# DB10005_PowerSwitch.net
KiCad netlist of a schematic drawn in Altium Designer
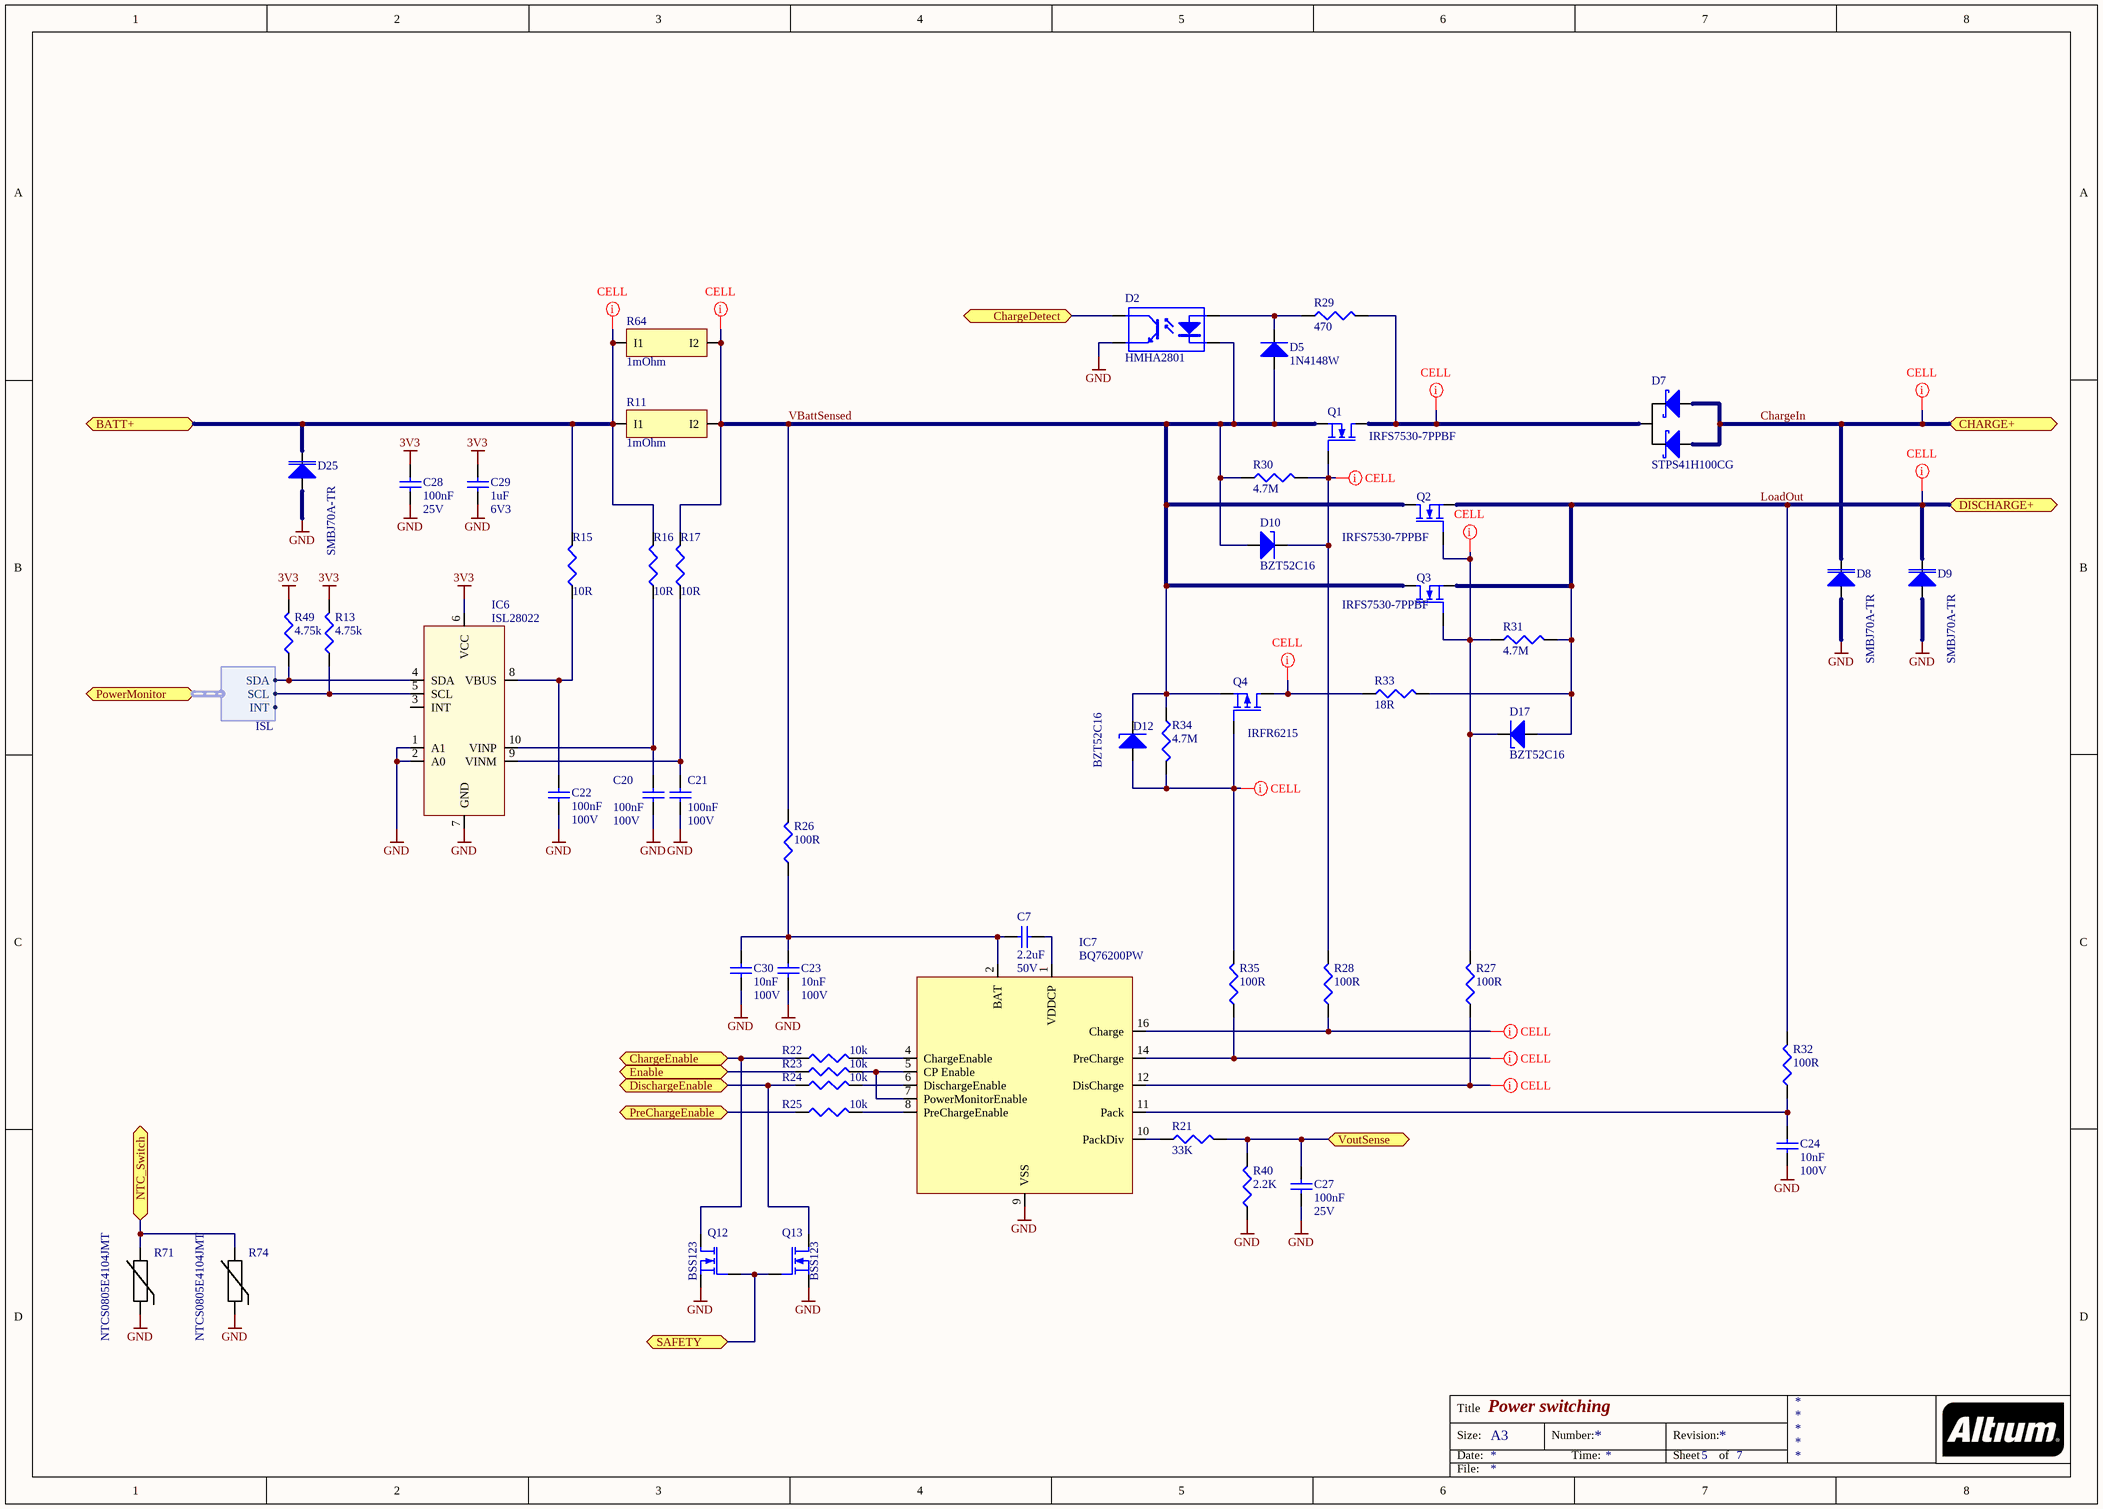
[diagram p0: DB10005_PowerSwitch.SchDoc]

(export (version "E")
  (design (tool "Eeschema 10.0.6"))
  (components
    (comp (ref "C7")
      (value "2.2uF")
      (footprint "C-0805")
      (description "Capacitor, 2.2uF, 50V,  X7R")
      (fields (field (name "VOLTAGE RATING") "50V"))
      (libsource (lib "AR_Capacitors_Ceramic") (part "2.2uF/0805/CER/50V"))
    )
    (comp (ref "C20")
      (value "100nF")
      (footprint "C-0805")
      (description "Capacitor, 100nF, 100V, X7R")
      (fields (field (name "VOLTAGE RATING") "100V"))
      (libsource (lib "AR_Capacitors_Ceramic") (part "100nF/0805/CER/100V"))
    )
    (comp (ref "C21")
      (value "100nF")
      (footprint "C-0805")
      (description "Capacitor, 100nF, 100V, X7R")
      (fields (field (name "VOLTAGE RATING") "100V"))
      (libsource (lib "AR_Capacitors_Ceramic") (part "100nF/0805/CER/100V"))
    )
    (comp (ref "C22")
      (value "100nF")
      (footprint "C-0805")
      (description "Capacitor, 100nF, 100V, X7R")
      (fields (field (name "VOLTAGE RATING") "100V"))
      (libsource (lib "AR_Capacitors_Ceramic") (part "100nF/0805/CER/100V"))
    )
    (comp (ref "C23")
      (value "10nF")
      (footprint "C-0805")
      (description "Capacitor, 10nF, 100V, X7R")
      (fields (field (name "VOLTAGE RATING") "100V"))
      (libsource (lib "AR_Capacitors_Ceramic") (part "10nF/0805/CER/100V"))
    )
    (comp (ref "C24")
      (value "10nF")
      (footprint "C-0805")
      (description "Capacitor, 10nF, 100V, X7R")
      (fields (field (name "VOLTAGE RATING") "100V"))
      (libsource (lib "AR_Capacitors_Ceramic") (part "10nF/0805/CER/100V"))
    )
    (comp (ref "C27")
      (value "100nF")
      (footprint "C0402")
      (description "Capacitor, 100nF, 25V, X7R")
      (fields (field (name "VOLTAGE RATING") "25V"))
      (libsource (lib "AR_Capacitors_Ceramic") (part "100nF/0402/CER/25V"))
    )
    (comp (ref "C28")
      (value "100nF")
      (footprint "C0402")
      (description "Capacitor, 100nF, 25V, X7R")
      (fields (field (name "VOLTAGE RATING") "25V"))
      (libsource (lib "AR_Capacitors_Ceramic") (part "100nF/0402/CER/25V"))
    )
    (comp (ref "C29")
      (value "1uF")
      (footprint "C0402")
      (description "Capacitor, 1uF, 6.3V, X5R")
      (fields (field (name "VOLTAGE RATING") "6V3"))
      (libsource (lib "AR_Capacitors_Ceramic") (part "1uF/0402/CER/6.3V"))
    )
    (comp (ref "C30")
      (value "10nF")
      (footprint "C-0805")
      (description "Capacitor, 10nF, 100V, X7R")
      (fields (field (name "VOLTAGE RATING") "100V"))
      (libsource (lib "AR_Capacitors_Ceramic") (part "10nF/0805/CER/100V"))
    )
    (comp (ref "D2")
      (value "HMHA2801")
      (footprint "FSOP4")
      (description "Optocoupler, Vout:80V, Iin:0.01A")
      (libsource (lib "AR_Optocouplers") (part "HMHA2801"))
    )
    (comp (ref "D5")
      (value "1N4148W")
      (footprint "SOD123")
      (description "Diode, Vrrm: 100V, If: 0.15A, Vf: 1V")
      (libsource (lib "AR_Diodes") (part "MMSD4148T1G"))
    )
    (comp (ref "D7")
      (value "STPS41H100CG")
      (footprint "D2-PAK")
      (description "100 V, 40 A, TO-263, 3 Pins, 900 mV")
      (libsource (lib "AR_Diodes") (part "STPS41H100CG"))
    )
    (comp (ref "D8")
      (value "SMBJ70A-TR")
      (footprint "SMB")
      (description "Diode TVS, Vrwm: 70V, Vbr: 81.9V, Vc: 113V, Ippm: 27A")
      (libsource (lib "AR_Diodes") (part "SMBJ70A-TR"))
    )
    (comp (ref "D9")
      (value "SMBJ70A-TR")
      (footprint "SMB")
      (description "Diode TVS, Vrwm: 70V, Vbr: 81.9V, Vc: 113V, Ippm: 27A")
      (libsource (lib "AR_Diodes") (part "SMBJ70A-TR"))
    )
    (comp (ref "D10")
      (value "BZT52C16")
      (footprint "SOD123")
      (description "Diode Zener, Vz: 16V, If: 0.1A, Vf: 0.9V")
      (libsource (lib "AR_Diodes") (part "BZT52C16"))
    )
    (comp (ref "D12")
      (value "BZT52C16")
      (footprint "SOD123")
      (description "Diode Zener, Vz: 16V, If: 0.1A, Vf: 0.9V")
      (libsource (lib "AR_Diodes") (part "BZT52C16"))
    )
    (comp (ref "D17")
      (value "BZT52C16")
      (footprint "SOD123")
      (description "Diode Zener, Vz: 16V, If: 0.1A, Vf: 0.9V")
      (libsource (lib "AR_Diodes") (part "BZT52C16"))
    )
    (comp (ref "D25")
      (value "SMBJ70A-TR")
      (footprint "SMB")
      (description "Diode TVS, Vrwm: 70V, Vbr: 81.9V, Vc: 113V, Ippm: 27A")
      (libsource (lib "AR_Diodes") (part "SMBJ70A-TR"))
    )
    (comp (ref "IC6")
      (value "ISL28022")
      (footprint "MSOP10")
      (description "Current and voltage ADC")
      (libsource (lib "AR_ICs") (part "ISL28022"))
    )
    (comp (ref "IC7")
      (value "BQ76200PW")
      (footprint "TSSOP16")
      (description "Battery protector, Lead Acid")
      (libsource (lib "AR_ICs") (part "BQ76200PW"))
    )
    (comp (ref "Q1")
      (value "IRFS7530-7PPBF")
      (footprint "D2PAK7")
      (description "Mosfet, N-channel, Vds:60V, Id:338A, Vgs-th:3.7V, Rds-on:0.00115ohm")
      (libsource (lib "AR_Mosfets") (part "IRFS7530-7PPBF"))
    )
    (comp (ref "Q2")
      (value "IRFS7530-7PPBF")
      (footprint "D2PAK7")
      (description "Mosfet, N-channel, Vds:60V, Id:338A, Vgs-th:3.7V, Rds-on:0.00115ohm")
      (libsource (lib "AR_Mosfets") (part "IRFS7530-7PPBF"))
    )
    (comp (ref "Q3")
      (value "IRFS7530-7PPBF")
      (footprint "D2PAK7")
      (description "Mosfet, N-channel, Vds:60V, Id:338A, Vgs-th:3.7V, Rds-on:0.00115ohm")
      (libsource (lib "AR_Mosfets") (part "IRFS7530-7PPBF"))
    )
    (comp (ref "Q4")
      (value "IRFR6215")
      (footprint "D-PAK")
      (description "Mosfet, P-channel, Vds:150V, Id:13A, Vgs-th:4V, Rds-on:0.295ohm")
      (libsource (lib "AR_Mosfets") (part "IRFR6215TRPBF"))
    )
    (comp (ref "Q12")
      (value "BSS123")
      (footprint "SOT-23")
      (description "Mosfet, N-channel, Vds:100V, Id:0.15A, Vgs-th:2.8V, Rds-on:3.5ohm")
      (libsource (lib "AR_Mosfets") (part "BSS123"))
    )
    (comp (ref "Q13")
      (value "BSS123")
      (footprint "SOT-23")
      (description "Mosfet, N-channel, Vds:100V, Id:0.15A, Vgs-th:2.8V, Rds-on:3.5ohm")
      (libsource (lib "AR_Mosfets") (part "BSS123"))
    )
    (comp (ref "R11")
      (value "1mOhm")
      (footprint "FCSL110")
      (description "1mohm, 5 W, ± 5%, 4320 Wide")
      (libsource (lib "AR_Misc") (part "FCSL110R001JER"))
    )
    (comp (ref "R13")
      (value "4.75k")
      (footprint "0402")
      (description "Resistor, 4.75k, 0.1%, 0.0625W, 50V, 100PPM, 0402")
      (libsource (lib "AR_Resistors_SMD") (part "4.75k/0402/0063W/50V"))
    )
    (comp (ref "R15")
      (value "10R")
      (footprint "0603")
      (description "Resistor, 10R, 1%, 0.063W, 50V, 200PPM, 0603")
      (libsource (lib "AR_Resistors_SMD") (part "10/0603/0063W/50V"))
    )
    (comp (ref "R16")
      (value "10R")
      (footprint "0603")
      (description "Resistor, 10R, 1%, 0.063W, 50V, 200PPM, 0603")
      (libsource (lib "AR_Resistors_SMD") (part "10/0603/0063W/50V"))
    )
    (comp (ref "R17")
      (value "10R")
      (footprint "0603")
      (description "Resistor, 10R, 1%, 0.063W, 50V, 200PPM, 0603")
      (libsource (lib "AR_Resistors_SMD") (part "10/0603/0063W/50V"))
    )
    (comp (ref "R21")
      (value "33K")
      (footprint "0603")
      (description "Resistor, 33K, 1%, 0.063W, 50V, 100PPM, 0603")
      (libsource (lib "AR_Resistors_SMD") (part "33K/0603/0063W/50V"))
    )
    (comp (ref "R22")
      (value "10k")
      (footprint "0402")
      (description "Resistor, 10k, 0.1%, 0.0625W, 50V, 100PPM, 0402")
      (libsource (lib "AR_Resistors_SMD") (part "10k/0402/0063W/50V"))
    )
    (comp (ref "R23")
      (value "10k")
      (footprint "0402")
      (description "Resistor, 10k, 0.1%, 0.0625W, 50V, 100PPM, 0402")
      (libsource (lib "AR_Resistors_SMD") (part "10k/0402/0063W/50V"))
    )
    (comp (ref "R24")
      (value "10k")
      (footprint "0402")
      (description "Resistor, 10k, 0.1%, 0.0625W, 50V, 100PPM, 0402")
      (libsource (lib "AR_Resistors_SMD") (part "10k/0402/0063W/50V"))
    )
    (comp (ref "R25")
      (value "10k")
      (footprint "0402")
      (description "Resistor, 10k, 0.1%, 0.0625W, 50V, 100PPM, 0402")
      (libsource (lib "AR_Resistors_SMD") (part "10k/0402/0063W/50V"))
    )
    (comp (ref "R26")
      (value "100R")
      (footprint "0603")
      (description "Resistor, 100R, 1%, 0.063W, 50V, 200PPM, 0603")
      (libsource (lib "AR_Resistors_SMD") (part "100/0603/0063W/50V"))
    )
    (comp (ref "R27")
      (value "100R")
      (footprint "0805")
      (description "Resistor, 100R, 1%, 0.25W, 150V, 100PPM, 0805")
      (libsource (lib "AR_Resistors_SMD") (part "100/0805/0250W/150V"))
    )
    (comp (ref "R28")
      (value "100R")
      (footprint "0805")
      (description "Resistor, 100R, 1%, 0.25W, 150V, 100PPM, 0805")
      (libsource (lib "AR_Resistors_SMD") (part "100/0805/0250W/150V"))
    )
    (comp (ref "R29")
      (value "470")
      (footprint "0402")
      (description "Resistor, 470, 1%, 0.0625W, 50V, 100PPM, 0402")
      (libsource (lib "AR_Resistors_SMD") (part "470/0402/0063W/50V"))
    )
    (comp (ref "R30")
      (value "4.7M")
      (footprint "0805")
      (description "Resistor, 4.7M, 1%, 0.25W, 150V, 100PPM, 0805")
      (libsource (lib "AR_Resistors_SMD") (part "4.7M/0805/0250W/150V"))
    )
    (comp (ref "R31")
      (value "4.7M")
      (footprint "0805")
      (description "Resistor, 4.7M, 1%, 0.25W, 150V, 100PPM, 0805")
      (libsource (lib "AR_Resistors_SMD") (part "4.7M/0805/0250W/150V"))
    )
    (comp (ref "R32")
      (value "100R")
      (footprint "0603")
      (description "Resistor, 100R, 1%, 0.063W, 50V, 200PPM, 0603")
      (libsource (lib "AR_Resistors_SMD") (part "100/0603/0063W/50V"))
    )
    (comp (ref "R33")
      (value "18R")
      (footprint "SM_3")
      (description "Resistor Wirewound, 18R, 5%, 3W, 500V, 200PPM, SMW")
      (libsource (lib "AR_Resistors_SMD") (part "18"))
    )
    (comp (ref "R34")
      (value "4.7M")
      (footprint "0805")
      (description "Resistor, 4.7M, 1%, 0.25W, 150V, 100PPM, 0805")
      (libsource (lib "AR_Resistors_SMD") (part "4.7M/0805/0250W/150V"))
    )
    (comp (ref "R35")
      (value "100R")
      (footprint "0805")
      (description "Resistor, 100R, 1%, 0.25W, 150V, 100PPM, 0805")
      (libsource (lib "AR_Resistors_SMD") (part "100/0805/0250W/150V"))
    )
    (comp (ref "R40")
      (value "2.2K")
      (footprint "0603")
      (description "Resistor, 2.2K, 1%, 0.063W, 50V, 100PPM, 0603")
      (libsource (lib "AR_Resistors_SMD") (part "2.2K/0603/0063W/50V"))
    )
    (comp (ref "R49")
      (value "4.75k")
      (footprint "0402")
      (description "Resistor, 4.75k, 0.1%, 0.0625W, 50V, 100PPM, 0402")
      (libsource (lib "AR_Resistors_SMD") (part "4.75k/0402/0063W/50V"))
    )
    (comp (ref "R64")
      (value "1mOhm")
      (footprint "FCSL110")
      (description "1mohm, 5 W, ± 5%, 4320 Wide")
      (libsource (lib "AR_Misc") (part "FCSL110R001JER"))
    )
    (comp (ref "R71")
      (value "NTCS0805E4104JMT")
      (footprint "0805")
      (description "THERMISTOR, NTC, 100K, 5%")
      (libsource (lib "DannyLib") (part "NTCS0805E4104JMT"))
    )
    (comp (ref "R74")
      (value "NTCS0805E4104JMT")
      (footprint "0805")
      (description "THERMISTOR, NTC, 100K, 5%")
      (libsource (lib "DannyLib") (part "NTCS0805E4104JMT"))
    )
  )
  (nets
    (net (code "2") (name "/BATT+") (class "Default")
      (node (ref "D25") (pin "2") (pinfunction "2_2") (pintype "passive"))
      (node (ref "R11") (pin "0") (pinfunction "I1_0") (pintype "passive"))
      (node (ref "R15") (pin "2") (pinfunction "2_2") (pintype "passive"))
      (node (ref "R16") (pin "2") (pinfunction "2_2") (pintype "passive"))
      (node (ref "R64") (pin "0") (pinfunction "I1_0") (pintype "passive"))
    )
    (net (code "3") (name "/ChargeDetect") (class "Default")
      (node (ref "D2") (pin "4") (pinfunction "C1_4") (pintype "passive"))
    )
    (net (code "4") (name "/ChargeEnable") (class "Default")
      (node (ref "Q12") (pin "D") (pinfunction "D_D") (pintype "passive"))
      (node (ref "R22") (pin "1") (pinfunction "1_1") (pintype "passive"))
    )
    (net (code "5") (name "/ChargeIn") (class "Default")
      (node (ref "D7") (pin "A1") (pinfunction "A1_A1") (pintype "passive"))
      (node (ref "D7") (pin "A2") (pinfunction "A2_A2") (pintype "passive"))
      (node (ref "D8") (pin "2") (pinfunction "2_2") (pintype "passive"))
    )
    (net (code "6") (name "/DischargeEnable") (class "Default")
      (node (ref "Q13") (pin "D") (pinfunction "D_D") (pintype "passive"))
      (node (ref "R24") (pin "1") (pinfunction "1_1") (pintype "passive"))
    )
    (net (code "7") (name "/Enable") (class "Default")
      (node (ref "R23") (pin "1") (pinfunction "1_1") (pintype "passive"))
    )
    (net (code "8") (name "/LoadOut") (class "Default")
      (node (ref "D17") (pin "1") (pinfunction "A_1") (pintype "passive"))
      (node (ref "D9") (pin "2") (pinfunction "2_2") (pintype "passive"))
      (node (ref "Q2") (pin "S") (pinfunction "S_S") (pintype "passive"))
      (node (ref "Q3") (pin "S") (pinfunction "S_S") (pintype "passive"))
      (node (ref "R31") (pin "2") (pinfunction "2_2") (pintype "passive"))
      (node (ref "R32") (pin "2") (pinfunction "2_2") (pintype "passive"))
      (node (ref "R33") (pin "2") (pinfunction "2_2") (pintype "passive"))
    )
    (net (code "9") (name "/NTC_Switch") (class "Default")
      (node (ref "R71") (pin "2") (pinfunction "2_2") (pintype "passive"))
      (node (ref "R74") (pin "2") (pinfunction "2_2") (pintype "passive"))
    )
    (net (code "10") (name "/PreChargeEnable") (class "Default")
      (node (ref "R25") (pin "1") (pinfunction "1_1") (pintype "passive"))
    )
    (net (code "11") (name "/SAFETY") (class "Default")
      (node (ref "Q12") (pin "G") (pinfunction "G_G") (pintype "passive"))
      (node (ref "Q13") (pin "G") (pinfunction "G_G") (pintype "passive"))
    )
    (net (code "12") (name "/VBattSensed") (class "Default")
      (node (ref "D10") (pin "1") (pinfunction "A_1") (pintype "passive"))
      (node (ref "D12") (pin "2") (pinfunction "K_2") (pintype "passive"))
      (node (ref "D2") (pin "2") (pinfunction "K1_2") (pintype "passive"))
      (node (ref "D5") (pin "1") (pinfunction "A_1") (pintype "passive"))
      (node (ref "Q1") (pin "S") (pinfunction "S_S") (pintype "passive"))
      (node (ref "Q2") (pin "D") (pinfunction "D_D") (pintype "passive"))
      (node (ref "Q3") (pin "D") (pinfunction "D_D") (pintype "passive"))
      (node (ref "Q4") (pin "S") (pinfunction "S_S") (pintype "passive"))
      (node (ref "R11") (pin "1") (pinfunction "I2_1") (pintype "passive"))
      (node (ref "R17") (pin "2") (pinfunction "2_2") (pintype "passive"))
      (node (ref "R26") (pin "2") (pinfunction "2_2") (pintype "passive"))
      (node (ref "R30") (pin "1") (pinfunction "1_1") (pintype "passive"))
      (node (ref "R34") (pin "1") (pinfunction "1_1") (pintype "passive"))
      (node (ref "R64") (pin "1") (pinfunction "I2_1") (pintype "passive"))
    )
    (net (code "13") (name "/VoutSense") (class "Default")
      (node (ref "C27") (pin "2") (pinfunction "2_2") (pintype "passive"))
      (node (ref "R21") (pin "2") (pinfunction "2_2") (pintype "passive"))
      (node (ref "R40") (pin "2") (pinfunction "2_2") (pintype "passive"))
    )
    (net (code "15") (name "3V3") (class "Default")
      (node (ref "C28") (pin "2") (pinfunction "2_2") (pintype "passive"))
      (node (ref "C29") (pin "2") (pinfunction "2_2") (pintype "passive"))
      (node (ref "IC6") (pin "6") (pinfunction "VCC_6") (pintype "power_in"))
      (node (ref "R13") (pin "2") (pinfunction "2_2") (pintype "passive"))
      (node (ref "R49") (pin "2") (pinfunction "2_2") (pintype "passive"))
    )
    (net (code "16") (name "GND") (class "Default")
      (node (ref "C20") (pin "1") (pinfunction "1_1") (pintype "passive"))
      (node (ref "C21") (pin "1") (pinfunction "1_1") (pintype "passive"))
      (node (ref "C22") (pin "1") (pinfunction "1_1") (pintype "passive"))
      (node (ref "C23") (pin "1") (pinfunction "1_1") (pintype "passive"))
      (node (ref "C24") (pin "1") (pinfunction "1_1") (pintype "passive"))
      (node (ref "C27") (pin "1") (pinfunction "1_1") (pintype "passive"))
      (node (ref "C28") (pin "1") (pinfunction "1_1") (pintype "passive"))
      (node (ref "C29") (pin "1") (pinfunction "1_1") (pintype "passive"))
      (node (ref "C30") (pin "1") (pinfunction "1_1") (pintype "passive"))
      (node (ref "D2") (pin "3") (pinfunction "E1_3") (pintype "passive"))
      (node (ref "D25") (pin "1") (pinfunction "1_1") (pintype "passive"))
      (node (ref "D8") (pin "1") (pinfunction "1_1") (pintype "passive"))
      (node (ref "D9") (pin "1") (pinfunction "1_1") (pintype "passive"))
      (node (ref "IC6") (pin "1") (pinfunction "A1_1") (pintype "power_in"))
      (node (ref "IC6") (pin "2") (pinfunction "A0_2") (pintype "power_in"))
      (node (ref "IC6") (pin "7") (pinfunction "GND_7") (pintype "power_in"))
      (node (ref "IC7") (pin "9") (pinfunction "VSS_9") (pintype "passive"))
      (node (ref "Q12") (pin "S") (pinfunction "S_S") (pintype "passive"))
      (node (ref "Q13") (pin "S") (pinfunction "S_S") (pintype "passive"))
      (node (ref "R40") (pin "1") (pinfunction "1_1") (pintype "passive"))
      (node (ref "R71") (pin "1") (pinfunction "1_1") (pintype "passive"))
      (node (ref "R74") (pin "1") (pinfunction "1_1") (pintype "passive"))
    )
    (net (code "17") (name "Net-(D2-A1)") (class "Default")
      (node (ref "D2") (pin "1") (pinfunction "A1_1") (pintype "passive"))
      (node (ref "D5") (pin "2") (pinfunction "K_2") (pintype "passive"))
      (node (ref "R29") (pin "1") (pinfunction "1_1") (pintype "passive"))
    )
    (net (code "18") (name "Net-(D7-PadK)") (class "Default")
      (node (ref "D7") (pin "K") (pinfunction "K_K") (pintype "passive"))
      (node (ref "Q1") (pin "D") (pinfunction "D_D") (pintype "passive"))
      (node (ref "R29") (pin "2") (pinfunction "2_2") (pintype "passive"))
    )
    (net (code "19") (name "Net-(D10-K)") (class "Default")
      (node (ref "D10") (pin "2") (pinfunction "K_2") (pintype "passive"))
      (node (ref "Q1") (pin "G") (pinfunction "G_G") (pintype "passive"))
      (node (ref "R28") (pin "2") (pinfunction "2_2") (pintype "passive"))
      (node (ref "R30") (pin "2") (pinfunction "2_2") (pintype "passive"))
    )
    (net (code "20") (name "Net-(D12-A)") (class "Default")
      (node (ref "D12") (pin "1") (pinfunction "A_1") (pintype "passive"))
      (node (ref "Q4") (pin "G") (pinfunction "G_G") (pintype "passive"))
      (node (ref "R34") (pin "2") (pinfunction "2_2") (pintype "passive"))
      (node (ref "R35") (pin "2") (pinfunction "2_2") (pintype "passive"))
    )
    (net (code "21") (name "Net-(D17-K)") (class "Default")
      (node (ref "D17") (pin "2") (pinfunction "K_2") (pintype "passive"))
      (node (ref "Q2") (pin "G") (pinfunction "G_G") (pintype "passive"))
      (node (ref "Q3") (pin "G") (pinfunction "G_G") (pintype "passive"))
      (node (ref "R27") (pin "2") (pinfunction "2_2") (pintype "passive"))
      (node (ref "R31") (pin "1") (pinfunction "1_1") (pintype "passive"))
    )
    (net (code "22") (name "Net-(IC6-SCL)") (class "Default")
      (node (ref "IC6") (pin "5") (pinfunction "SCL_5") (pintype "power_in"))
      (node (ref "R13") (pin "1") (pinfunction "1_1") (pintype "passive"))
    )
    (net (code "23") (name "Net-(IC6-SDA)") (class "Default")
      (node (ref "IC6") (pin "4") (pinfunction "SDA_4") (pintype "power_in"))
      (node (ref "R49") (pin "1") (pinfunction "1_1") (pintype "passive"))
    )
    (net (code "24") (name "Net-(IC6-VBUS)") (class "Default")
      (node (ref "C22") (pin "2") (pinfunction "2_2") (pintype "passive"))
      (node (ref "IC6") (pin "8") (pinfunction "VBUS_8") (pintype "power_in"))
      (node (ref "R15") (pin "1") (pinfunction "1_1") (pintype "passive"))
    )
    (net (code "25") (name "Net-(IC6-VINM)") (class "Default")
      (node (ref "C21") (pin "2") (pinfunction "2_2") (pintype "passive"))
      (node (ref "IC6") (pin "9") (pinfunction "VINM_9") (pintype "power_in"))
      (node (ref "R17") (pin "1") (pinfunction "1_1") (pintype "passive"))
    )
    (net (code "26") (name "Net-(IC6-VINP)") (class "Default")
      (node (ref "C20") (pin "2") (pinfunction "2_2") (pintype "passive"))
      (node (ref "IC6") (pin "10") (pinfunction "VINP_10") (pintype "power_in"))
      (node (ref "R16") (pin "1") (pinfunction "1_1") (pintype "passive"))
    )
    (net (code "27") (name "Net-(IC7-BAT)") (class "Default")
      (node (ref "C23") (pin "2") (pinfunction "2_2") (pintype "passive"))
      (node (ref "C30") (pin "2") (pinfunction "2_2") (pintype "passive"))
      (node (ref "C7") (pin "1") (pinfunction "1_1") (pintype "passive"))
      (node (ref "IC7") (pin "2") (pinfunction "BAT_2") (pintype "passive"))
      (node (ref "R26") (pin "1") (pinfunction "1_1") (pintype "passive"))
    )
    (net (code "28") (name "Net-(IC7-CP_Enable)") (class "Default")
      (node (ref "IC7") (pin "5") (pinfunction "CP_Enable_5") (pintype "passive"))
      (node (ref "IC7") (pin "7") (pinfunction "PowerMonitorEnable_7") (pintype "passive"))
      (node (ref "R23") (pin "2") (pinfunction "2_2") (pintype "passive"))
    )
    (net (code "29") (name "Net-(IC7-Charge)") (class "Default")
      (node (ref "IC7") (pin "16") (pinfunction "Charge_16") (pintype "passive"))
      (node (ref "R28") (pin "1") (pinfunction "1_1") (pintype "passive"))
    )
    (net (code "30") (name "Net-(IC7-ChargeEnable)") (class "Default")
      (node (ref "IC7") (pin "4") (pinfunction "ChargeEnable_4") (pintype "passive"))
      (node (ref "R22") (pin "2") (pinfunction "2_2") (pintype "passive"))
    )
    (net (code "31") (name "Net-(IC7-DisCharge)") (class "Default")
      (node (ref "IC7") (pin "12") (pinfunction "DisCharge_12") (pintype "passive"))
      (node (ref "R27") (pin "1") (pinfunction "1_1") (pintype "passive"))
    )
    (net (code "32") (name "Net-(IC7-DischargeEnable)") (class "Default")
      (node (ref "IC7") (pin "6") (pinfunction "DischargeEnable_6") (pintype "passive"))
      (node (ref "R24") (pin "2") (pinfunction "2_2") (pintype "passive"))
    )
    (net (code "33") (name "Net-(IC7-Pack)") (class "Default")
      (node (ref "C24") (pin "2") (pinfunction "2_2") (pintype "passive"))
      (node (ref "IC7") (pin "11") (pinfunction "Pack_11") (pintype "passive"))
      (node (ref "R32") (pin "1") (pinfunction "1_1") (pintype "passive"))
    )
    (net (code "34") (name "Net-(IC7-PackDiv)") (class "Default")
      (node (ref "IC7") (pin "10") (pinfunction "PackDiv_10") (pintype "passive"))
      (node (ref "R21") (pin "1") (pinfunction "1_1") (pintype "passive"))
    )
    (net (code "35") (name "Net-(IC7-PreCharge)") (class "Default")
      (node (ref "IC7") (pin "14") (pinfunction "PreCharge_14") (pintype "passive"))
      (node (ref "R35") (pin "1") (pinfunction "1_1") (pintype "passive"))
    )
    (net (code "36") (name "Net-(IC7-PreChargeEnable)") (class "Default")
      (node (ref "IC7") (pin "8") (pinfunction "PreChargeEnable_8") (pintype "passive"))
      (node (ref "R25") (pin "2") (pinfunction "2_2") (pintype "passive"))
    )
    (net (code "37") (name "Net-(IC7-VDDCP)") (class "Default")
      (node (ref "C7") (pin "2") (pinfunction "2_2") (pintype "passive"))
      (node (ref "IC7") (pin "1") (pinfunction "VDDCP_1") (pintype "passive"))
    )
    (net (code "38") (name "Net-(Q4-PadD)") (class "Default")
      (node (ref "Q4") (pin "D") (pinfunction "D_D") (pintype "passive"))
      (node (ref "R33") (pin "1") (pinfunction "1_1") (pintype "passive"))
    )
    (net (code "39") (name "unconnected-(IC6-INT-Pad3)") (class "Default")
      (node (ref "IC6") (pin "3") (pinfunction "INT_3") (pintype "power_in"))
    )
  )
)
